# Pointcast_upper_board_V1_02.net
KiCad netlist of a schematic drawn in EAGLE
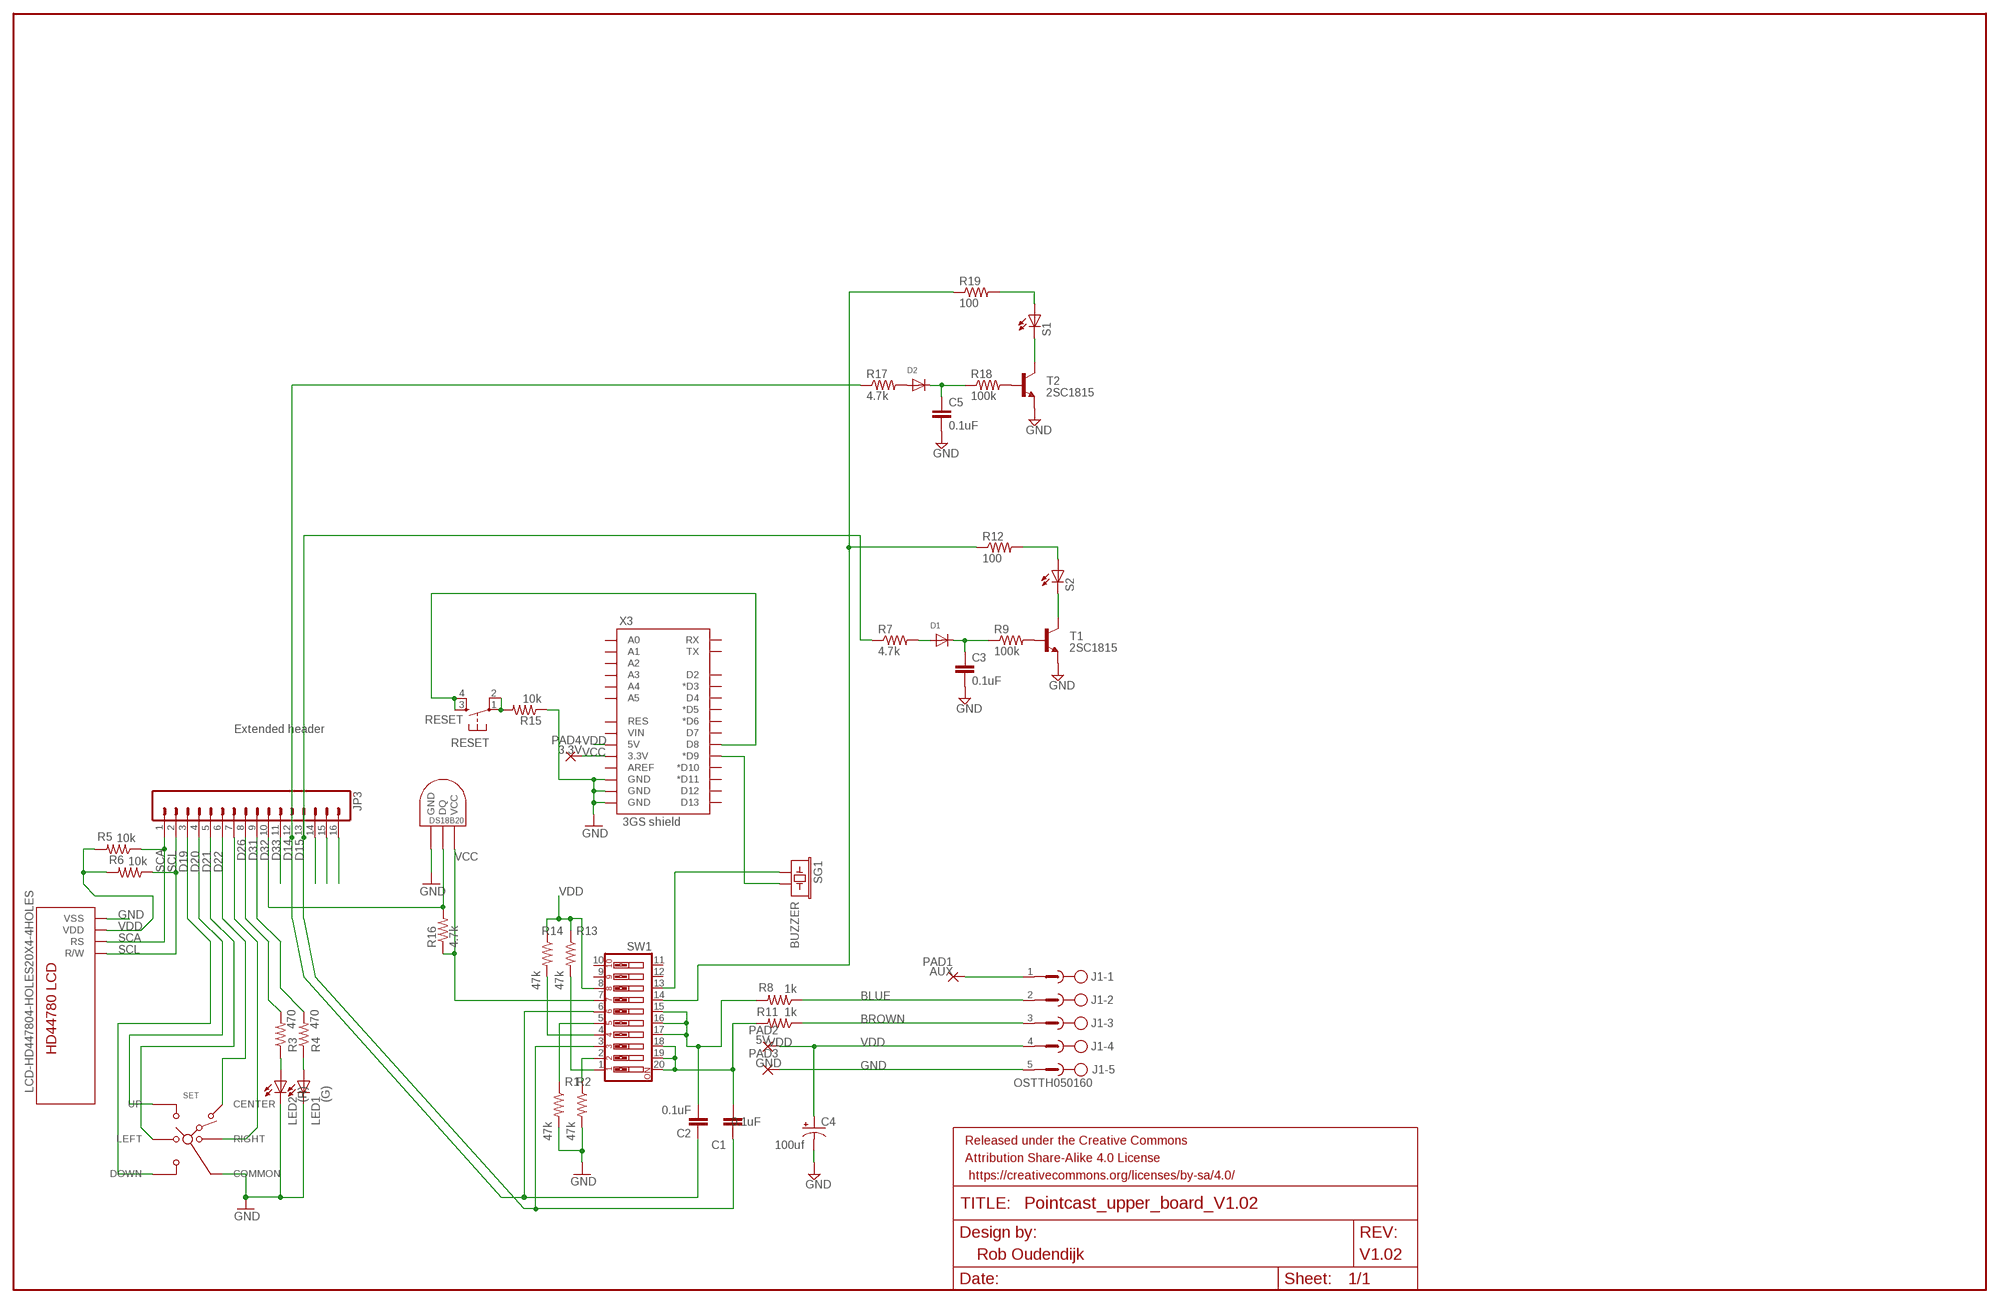
[diagram p0: schematic, sheet 1]

(export (version "E")
  (design (tool "Eeschema 10.0.6"))
  (components
    (comp (ref "C1")
      (value "0.1uF")
      (footprint "eagle-import:C025-024X044")
      (libsource (lib "eagle-import") (part "C-EU025-024X044"))
    )
    (comp (ref "C2")
      (value "0.1uF")
      (footprint "eagle-import:C025-024X044")
      (libsource (lib "eagle-import") (part "C-EU025-024X044"))
    )
    (comp (ref "C3")
      (value "0.1uF")
      (footprint "eagle-import:C025-024X044")
      (libsource (lib "eagle-import") (part "C-EU025-024X044"))
    )
    (comp (ref "C4")
      (value "100uf")
      (footprint "eagle-import:CPOL-RADIAL-100UF-25V")
      (libsource (lib "eagle-import") (part "CAP_POLPTH1"))
    )
    (comp (ref "C5")
      (value "0.1uF")
      (footprint "eagle-import:C025-024X044")
      (libsource (lib "eagle-import") (part "C-EU025-024X044"))
    )
    (comp (ref "D1")
      (value "DIODEDIODE_BIG")
      (footprint "eagle-import:DO41-10")
      (libsource (lib "eagle-import") (part "DIODEDIODE_BIG"))
    )
    (comp (ref "D2")
      (value "DIODEDIODE_BIG")
      (footprint "eagle-import:DO41-10")
      (libsource (lib "eagle-import") (part "DIODEDIODE_BIG"))
    )
    (comp (ref "FRAME1")
      (value "FRAME-LEDGER")
      (footprint "eagle-import:CREATIVE_COMMONS")
      (libsource (lib "eagle-import") (part "FRAME-LEDGER"))
    )
    (comp (ref "J1")
      (value "OSTTH050160")
      (footprint "eagle-import:EDSTL130-05")
      (libsource (lib "eagle-import") (part "OSTTH050160"))
    )
    (comp (ref "JP3")
      (value "Extended header")
      (footprint "eagle-import:1X16")
      (libsource (lib "eagle-import") (part "M16PTH"))
    )
    (comp (ref "LED1")
      (value "(G)")
      (footprint "eagle-import:LED3MM")
      (libsource (lib "eagle-import") (part "LED3MM"))
    )
    (comp (ref "LED2")
      (value "(R)")
      (footprint "eagle-import:LED3MM")
      (libsource (lib "eagle-import") (part "LED3MM"))
    )
    (comp (ref "PAD1")
      (value "AUX")
      (footprint "eagle-import:2,15_1,0")
      (libsource (lib "eagle-import") (part "2,15/1,0"))
    )
    (comp (ref "PAD2")
      (value "5V")
      (footprint "eagle-import:2,15_1,0")
      (libsource (lib "eagle-import") (part "2,15/1,0"))
    )
    (comp (ref "PAD3")
      (value "GND")
      (footprint "eagle-import:2,15_1,0")
      (libsource (lib "eagle-import") (part "2,15/1,0"))
    )
    (comp (ref "PAD4")
      (value "3.3V")
      (footprint "eagle-import:2,15_1,0")
      (libsource (lib "eagle-import") (part "2,15/1,0"))
    )
    (comp (ref "R1")
      (value "47k")
      (footprint "eagle-import:0207_10")
      (libsource (lib "eagle-import") (part "resistor_R-US_0207/10"))
    )
    (comp (ref "R2")
      (value "47k")
      (footprint "eagle-import:0207_10")
      (libsource (lib "eagle-import") (part "resistor_R-US_0207/10"))
    )
    (comp (ref "R3")
      (value "470")
      (footprint "eagle-import:0207_10")
      (libsource (lib "eagle-import") (part "resistor_R-US_0207/10"))
    )
    (comp (ref "R4")
      (value "470")
      (footprint "eagle-import:0207_10")
      (libsource (lib "eagle-import") (part "resistor_R-US_0207/10"))
    )
    (comp (ref "R5")
      (value "10k")
      (footprint "eagle-import:0207_10")
      (libsource (lib "eagle-import") (part "R-US_0207/10"))
    )
    (comp (ref "R6")
      (value "10k")
      (footprint "eagle-import:0207_10")
      (libsource (lib "eagle-import") (part "R-US_0207/10"))
    )
    (comp (ref "R7")
      (value "4.7k")
      (footprint "eagle-import:0207_10")
      (libsource (lib "eagle-import") (part "rcl_R-US_0207/10"))
    )
    (comp (ref "R8")
      (value "1k")
      (footprint "eagle-import:0207_10")
      (libsource (lib "eagle-import") (part "resistor_R-US_0207/10"))
    )
    (comp (ref "R9")
      (value "100k")
      (footprint "eagle-import:0207_10")
      (libsource (lib "eagle-import") (part "rcl_R-US_0207/10"))
    )
    (comp (ref "R11")
      (value "1k")
      (footprint "eagle-import:0207_10")
      (libsource (lib "eagle-import") (part "resistor_R-US_0207/10"))
    )
    (comp (ref "R12")
      (value "100")
      (footprint "eagle-import:0207_10")
      (libsource (lib "eagle-import") (part "rcl_R-US_0207/10"))
    )
    (comp (ref "R13")
      (value "47k")
      (footprint "eagle-import:0207_10")
      (libsource (lib "eagle-import") (part "resistor_R-US_0207/10"))
    )
    (comp (ref "R14")
      (value "47k")
      (footprint "eagle-import:0207_10")
      (libsource (lib "eagle-import") (part "resistor_R-US_0207/10"))
    )
    (comp (ref "R15")
      (value "10k")
      (footprint "eagle-import:0207_10")
      (libsource (lib "eagle-import") (part "resistor_R-US_0207/10"))
    )
    (comp (ref "R16")
      (value "4.7k")
      (footprint "eagle-import:0207_10")
      (libsource (lib "eagle-import") (part "resistor_R-US_0207/10"))
    )
    (comp (ref "R17")
      (value "4.7k")
      (footprint "eagle-import:0207_10")
      (libsource (lib "eagle-import") (part "rcl_R-US_0207/10"))
    )
    (comp (ref "R18")
      (value "100k")
      (footprint "eagle-import:0207_10")
      (libsource (lib "eagle-import") (part "rcl_R-US_0207/10"))
    )
    (comp (ref "R19")
      (value "100")
      (footprint "eagle-import:0207_10")
      (libsource (lib "eagle-import") (part "rcl_R-US_0207/10"))
    )
    (comp (ref "RESET")
      (value "RESET")
      (footprint "eagle-import:DTS-6")
      (libsource (lib "eagle-import") (part "DTS-6"))
    )
    (comp (ref "S1")
      (value "LED3MM")
      (footprint "eagle-import:LED3MM")
      (libsource (lib "eagle-import") (part "LED3MM"))
    )
    (comp (ref "S2")
      (value "LED3MM")
      (footprint "eagle-import:LED3MM")
      (libsource (lib "eagle-import") (part "LED3MM"))
    )
    (comp (ref "SET")
      (value "SKQUCAA010")
      (footprint "eagle-import:SKQU")
      (fields (field (name "MF") "ALPS"))
      (libsource (lib "eagle-import") (part "SKQUCAA010"))
    )
    (comp (ref "SG1")
      (value "BUZZER")
      (footprint "eagle-import:BUZZER-12MM")
      (libsource (lib "eagle-import") (part "BUZZERPTH"))
    )
    (comp (ref "SW1")
      (value "SW_DIP-10")
      (footprint "eagle-import:EDG-10")
      (libsource (lib "eagle-import") (part "SW_DIP-10"))
    )
    (comp (ref "T1")
      (value "2SC1815")
      (footprint "eagle-import:TO92-ECB")
      (libsource (lib "eagle-import") (part "2SC1815"))
    )
    (comp (ref "T2")
      (value "2SC1815")
      (footprint "eagle-import:TO92-ECB")
      (libsource (lib "eagle-import") (part "2SC1815"))
    )
    (comp (ref "TEMP")
      (value "AVA_DS1820TO92")
      (footprint "eagle-import:AVA_DS1820")
      (libsource (lib "eagle-import") (part "AVA_DS1820TO92"))
    )
    (comp (ref "X1")
      (value "LCD-HD447804-HOLES20X4-4HOLES")
      (footprint "eagle-import:LCD-20X4-4HOLES")
      (libsource (lib "eagle-import") (part "LCD-HD4478020X4-4HOLES4-HOLES"))
    )
    (comp (ref "X3")
      (value "3GS shield")
      (footprint "eagle-import:DUEMILANOVE_SHIELD")
      (libsource (lib "eagle-import") (part "ARDUINO_SHIELDLABEL"))
    )
  )
  (nets
    (net (code "1") (name "/BLUE") (class "Default")
      (node (ref "J1") (pin "2") (pinfunction "SK_2") (pintype "passive"))
      (node (ref "R8") (pin "1") (pinfunction "1_1") (pintype "passive"))
    )
    (net (code "2") (name "/BROWN") (class "Default")
      (node (ref "J1") (pin "3") (pinfunction "SK_3") (pintype "passive"))
      (node (ref "R11") (pin "1") (pinfunction "1_1") (pintype "passive"))
    )
    (net (code "3") (name "/D14") (class "Default")
      (node (ref "C2") (pin "1") (pinfunction "1_1") (pintype "passive"))
      (node (ref "JP3") (pin "12") (pinfunction "12_12") (pintype "passive"))
      (node (ref "R17") (pin "1") (pinfunction "1_1") (pintype "passive"))
      (node (ref "SW1") (pin "6") (pinfunction "6_6") (pintype "passive"))
    )
    (net (code "4") (name "/D15") (class "Default")
      (node (ref "C1") (pin "1") (pinfunction "1_1") (pintype "passive"))
      (node (ref "JP3") (pin "13") (pinfunction "13_13") (pintype "passive"))
      (node (ref "R7") (pin "1") (pinfunction "1_1") (pintype "passive"))
      (node (ref "SW1") (pin "3") (pinfunction "3_3") (pintype "passive"))
    )
    (net (code "5") (name "/D19") (class "Default")
      (node (ref "JP3") (pin "3") (pinfunction "3_3") (pintype "passive"))
      (node (ref "SET") (pin "DOWN") (pinfunction "DOWN_DOWN") (pintype "passive"))
    )
    (net (code "6") (name "/D20") (class "Default")
      (node (ref "JP3") (pin "4") (pinfunction "4_4") (pintype "passive"))
      (node (ref "SET") (pin "UP") (pinfunction "UP_UP") (pintype "passive"))
    )
    (net (code "7") (name "/D21") (class "Default")
      (node (ref "JP3") (pin "5") (pinfunction "5_5") (pintype "passive"))
      (node (ref "SET") (pin "LEFT") (pinfunction "LEFT_LEFT") (pintype "passive"))
    )
    (net (code "8") (name "/D22") (class "Default")
      (node (ref "JP3") (pin "6") (pinfunction "6_6") (pintype "passive"))
      (node (ref "SET") (pin "CENTER") (pinfunction "CENTER_CENTER") (pintype "passive"))
    )
    (net (code "9") (name "/D26") (class "Default")
      (node (ref "JP3") (pin "8") (pinfunction "8_8") (pintype "passive"))
      (node (ref "R3") (pin "2") (pinfunction "2_2") (pintype "passive"))
    )
    (net (code "10") (name "/D31") (class "Default")
      (node (ref "JP3") (pin "9") (pinfunction "9_9") (pintype "passive"))
      (node (ref "R4") (pin "2") (pinfunction "2_2") (pintype "passive"))
    )
    (net (code "11") (name "/D32") (class "Default")
      (node (ref "JP3") (pin "10") (pinfunction "10_10") (pintype "passive"))
      (node (ref "R16") (pin "2") (pinfunction "2_2") (pintype "passive"))
      (node (ref "TEMP") (pin "DQ") (pinfunction "DQ_DQ") (pintype "bidirectional"))
    )
    (net (code "12") (name "/D33") (class "Default")
      (node (ref "JP3") (pin "11") (pinfunction "11_11") (pintype "passive"))
    )
    (net (code "13") (name "/SCA") (class "Default")
      (node (ref "JP3") (pin "1") (pinfunction "1_1") (pintype "passive"))
      (node (ref "R5") (pin "1") (pinfunction "1_1") (pintype "passive"))
      (node (ref "X1") (pin "P$15") (pinfunction "RS_P$15") (pintype "input"))
    )
    (net (code "14") (name "/SCL") (class "Default")
      (node (ref "JP3") (pin "2") (pinfunction "2_2") (pintype "passive"))
      (node (ref "R6") (pin "1") (pinfunction "1_1") (pintype "passive"))
      (node (ref "X1") (pin "P$16") (pinfunction "R/W_P$16") (pintype "input"))
    )
    (net (code "15") (name "/VCC") (class "Default")
      (node (ref "PAD4") (pin "1") (pinfunction "P_1") (pintype "passive"))
      (node (ref "R16") (pin "1") (pinfunction "1_1") (pintype "passive"))
      (node (ref "SW1") (pin "7") (pinfunction "7_7") (pintype "passive"))
      (node (ref "TEMP") (pin "VDD") (pinfunction "VCC_VDD") (pintype "power_in"))
      (node (ref "X3") (pin "3.3V") (pinfunction "3.3V_3.3V") (pintype "bidirectional"))
    )
    (net (code "16") (name "/VDD") (class "Default")
      (node (ref "C4") (pin "2") (pinfunction "+_2") (pintype "passive"))
      (node (ref "J1") (pin "4") (pinfunction "SK_4") (pintype "passive"))
      (node (ref "PAD2") (pin "1") (pinfunction "P_1") (pintype "passive"))
      (node (ref "R13") (pin "1") (pinfunction "1_1") (pintype "passive"))
      (node (ref "R14") (pin "1") (pinfunction "1_1") (pintype "passive"))
      (node (ref "R5") (pin "2") (pinfunction "2_2") (pintype "passive"))
      (node (ref "R6") (pin "2") (pinfunction "2_2") (pintype "passive"))
      (node (ref "SW1") (pin "8") (pinfunction "8_8") (pintype "passive"))
      (node (ref "X1") (pin "P$14") (pinfunction "VDD_P$14") (pintype "power_in"))
      (node (ref "X3") (pin "5V") (pinfunction "5V_5V") (pintype "bidirectional"))
    )
    (net (code "17") (name "GND") (class "Default")
      (node (ref "C3") (pin "2") (pinfunction "2_2") (pintype "passive"))
      (node (ref "C4") (pin "1") (pinfunction "-_1") (pintype "passive"))
      (node (ref "C5") (pin "2") (pinfunction "2_2") (pintype "passive"))
      (node (ref "J1") (pin "5") (pinfunction "SK_5") (pintype "passive"))
      (node (ref "LED1") (pin "K") (pinfunction "C_K") (pintype "passive"))
      (node (ref "LED2") (pin "K") (pinfunction "C_K") (pintype "passive"))
      (node (ref "PAD3") (pin "1") (pinfunction "P_1") (pintype "passive"))
      (node (ref "R1") (pin "2") (pinfunction "2_2") (pintype "passive"))
      (node (ref "R15") (pin "1") (pinfunction "1_1") (pintype "passive"))
      (node (ref "R2") (pin "2") (pinfunction "2_2") (pintype "passive"))
      (node (ref "SET") (pin "COMMON") (pinfunction "COMMON_COMMON") (pintype "power_in"))
      (node (ref "T1") (pin "E") (pinfunction "E_E") (pintype "passive"))
      (node (ref "T2") (pin "E") (pinfunction "E_E") (pintype "passive"))
      (node (ref "TEMP") (pin "GND") (pinfunction "GND_GND") (pintype "power_in"))
      (node (ref "X1") (pin "P$13") (pinfunction "VSS_P$13") (pintype "power_in"))
      (node (ref "X3") (pin "GND@0") (pinfunction "GND_GND@0") (pintype "bidirectional"))
      (node (ref "X3") (pin "GND@1") (pinfunction "GND_GND@1") (pintype "bidirectional"))
      (node (ref "X3") (pin "GND@2") (pinfunction "GND_GND@2") (pintype "bidirectional"))
    )
    (net (code "18") (name "Net-(C1-Pad2)") (class "Default")
      (node (ref "C1") (pin "2") (pinfunction "2_2") (pintype "passive"))
      (node (ref "R11") (pin "2") (pinfunction "2_2") (pintype "passive"))
      (node (ref "SW1") (pin "18") (pinfunction "18_18") (pintype "passive"))
      (node (ref "SW1") (pin "19") (pinfunction "19_19") (pintype "passive"))
      (node (ref "SW1") (pin "20") (pinfunction "20_20") (pintype "passive"))
    )
    (net (code "19") (name "Net-(C2-Pad2)") (class "Default")
      (node (ref "C2") (pin "2") (pinfunction "2_2") (pintype "passive"))
      (node (ref "R8") (pin "2") (pinfunction "2_2") (pintype "passive"))
      (node (ref "SW1") (pin "15") (pinfunction "15_15") (pintype "passive"))
      (node (ref "SW1") (pin "16") (pinfunction "16_16") (pintype "passive"))
      (node (ref "SW1") (pin "17") (pinfunction "17_17") (pintype "passive"))
    )
    (net (code "20") (name "Net-(C3-Pad1)") (class "Default")
      (node (ref "C3") (pin "1") (pinfunction "1_1") (pintype "passive"))
      (node (ref "D1") (pin "C") (pinfunction "C_C") (pintype "passive"))
      (node (ref "R9") (pin "1") (pinfunction "1_1") (pintype "passive"))
    )
    (net (code "21") (name "Net-(C5-Pad1)") (class "Default")
      (node (ref "C5") (pin "1") (pinfunction "1_1") (pintype "passive"))
      (node (ref "D2") (pin "C") (pinfunction "C_C") (pintype "passive"))
      (node (ref "R18") (pin "1") (pinfunction "1_1") (pintype "passive"))
    )
    (net (code "22") (name "Net-(D1-PadA)") (class "Default")
      (node (ref "D1") (pin "A") (pinfunction "A_A") (pintype "passive"))
      (node (ref "R7") (pin "2") (pinfunction "2_2") (pintype "passive"))
    )
    (net (code "23") (name "Net-(D2-PadA)") (class "Default")
      (node (ref "D2") (pin "A") (pinfunction "A_A") (pintype "passive"))
      (node (ref "R17") (pin "2") (pinfunction "2_2") (pintype "passive"))
    )
    (net (code "24") (name "Net-(J1A-SK)") (class "Default")
      (node (ref "J1") (pin "1") (pinfunction "SK_1") (pintype "passive"))
      (node (ref "PAD1") (pin "1") (pinfunction "P_1") (pintype "passive"))
    )
    (net (code "25") (name "Net-(JP3-Pad7)") (class "Default")
      (node (ref "JP3") (pin "7") (pinfunction "7_7") (pintype "passive"))
      (node (ref "SET") (pin "RIGHT") (pinfunction "RIGHT_RIGHT") (pintype "passive"))
    )
    (net (code "26") (name "Net-(LED1-PadA)") (class "Default")
      (node (ref "LED1") (pin "A") (pinfunction "A_A") (pintype "passive"))
      (node (ref "R4") (pin "1") (pinfunction "1_1") (pintype "passive"))
    )
    (net (code "27") (name "Net-(LED2-PadA)") (class "Default")
      (node (ref "LED2") (pin "A") (pinfunction "A_A") (pintype "passive"))
      (node (ref "R3") (pin "1") (pinfunction "1_1") (pintype "passive"))
    )
    (net (code "28") (name "Net-(R1-Pad1)") (class "Default")
      (node (ref "R1") (pin "1") (pinfunction "1_1") (pintype "passive"))
      (node (ref "SW1") (pin "5") (pinfunction "5_5") (pintype "passive"))
    )
    (net (code "29") (name "Net-(R2-Pad1)") (class "Default")
      (node (ref "R2") (pin "1") (pinfunction "1_1") (pintype "passive"))
      (node (ref "SW1") (pin "2") (pinfunction "2_2") (pintype "passive"))
    )
    (net (code "30") (name "Net-(R9-Pad2)") (class "Default")
      (node (ref "R9") (pin "2") (pinfunction "2_2") (pintype "passive"))
      (node (ref "T1") (pin "B") (pinfunction "B_B") (pintype "passive"))
    )
    (net (code "31") (name "Net-(R12-Pad1)") (class "Default")
      (node (ref "R12") (pin "1") (pinfunction "1_1") (pintype "passive"))
      (node (ref "R19") (pin "1") (pinfunction "1_1") (pintype "passive"))
      (node (ref "SW1") (pin "14") (pinfunction "14_14") (pintype "passive"))
    )
    (net (code "32") (name "Net-(R12-Pad2)") (class "Default")
      (node (ref "R12") (pin "2") (pinfunction "2_2") (pintype "passive"))
      (node (ref "S2") (pin "A") (pinfunction "A_A") (pintype "passive"))
    )
    (net (code "33") (name "Net-(R13-Pad2)") (class "Default")
      (node (ref "R13") (pin "2") (pinfunction "2_2") (pintype "passive"))
      (node (ref "SW1") (pin "1") (pinfunction "1_1") (pintype "passive"))
    )
    (net (code "34") (name "Net-(R14-Pad2)") (class "Default")
      (node (ref "R14") (pin "2") (pinfunction "2_2") (pintype "passive"))
      (node (ref "SW1") (pin "4") (pinfunction "4_4") (pintype "passive"))
    )
    (net (code "35") (name "Net-(R15-Pad2)") (class "Default")
      (node (ref "R15") (pin "2") (pinfunction "2_2") (pintype "passive"))
      (node (ref "RESET") (pin "1") (pinfunction "1_1") (pintype "passive"))
      (node (ref "RESET") (pin "2") (pinfunction "2_2") (pintype "passive"))
    )
    (net (code "36") (name "Net-(R18-Pad2)") (class "Default")
      (node (ref "R18") (pin "2") (pinfunction "2_2") (pintype "passive"))
      (node (ref "T2") (pin "B") (pinfunction "B_B") (pintype "passive"))
    )
    (net (code "37") (name "Net-(R19-Pad2)") (class "Default")
      (node (ref "R19") (pin "2") (pinfunction "2_2") (pintype "passive"))
      (node (ref "S1") (pin "A") (pinfunction "A_A") (pintype "passive"))
    )
    (net (code "38") (name "Net-(RESET-Pad3)") (class "Default")
      (node (ref "RESET") (pin "3") (pinfunction "3_3") (pintype "passive"))
      (node (ref "RESET") (pin "4") (pinfunction "4_4") (pintype "passive"))
      (node (ref "X3") (pin "D8") (pinfunction "D8_D8") (pintype "bidirectional"))
    )
    (net (code "39") (name "Net-(S1-C)") (class "Default")
      (node (ref "S1") (pin "K") (pinfunction "C_K") (pintype "passive"))
      (node (ref "T2") (pin "C") (pinfunction "C_C") (pintype "passive"))
    )
    (net (code "40") (name "Net-(S2-C)") (class "Default")
      (node (ref "S2") (pin "K") (pinfunction "C_K") (pintype "passive"))
      (node (ref "T1") (pin "C") (pinfunction "C_C") (pintype "passive"))
    )
    (net (code "41") (name "Net-(SG1-1)") (class "Default")
      (node (ref "SG1") (pin "+") (pinfunction "1_+") (pintype "passive"))
      (node (ref "SW1") (pin "13") (pinfunction "13_13") (pintype "passive"))
    )
    (net (code "42") (name "Net-(SG1-2)") (class "Default")
      (node (ref "SG1") (pin "-") (pinfunction "2_-") (pintype "passive"))
      (node (ref "X3") (pin "D9") (pinfunction "*D9_D9") (pintype "bidirectional"))
    )
    (net (code "43") (name "unconnected-(JP3-Pad14)") (class "Default")
      (node (ref "JP3") (pin "14") (pinfunction "14_14") (pintype "passive"))
    )
    (net (code "44") (name "unconnected-(JP3-Pad15)") (class "Default")
      (node (ref "JP3") (pin "15") (pinfunction "15_15") (pintype "passive"))
    )
    (net (code "45") (name "unconnected-(JP3-Pad16)") (class "Default")
      (node (ref "JP3") (pin "16") (pinfunction "16_16") (pintype "passive"))
    )
    (net (code "46") (name "unconnected-(SW1-Pad9)") (class "Default")
      (node (ref "SW1") (pin "9") (pinfunction "9_9") (pintype "passive"))
    )
    (net (code "47") (name "unconnected-(SW1-Pad10)") (class "Default")
      (node (ref "SW1") (pin "10") (pinfunction "10_10") (pintype "passive"))
    )
    (net (code "48") (name "unconnected-(SW1-Pad11)") (class "Default")
      (node (ref "SW1") (pin "11") (pinfunction "11_11") (pintype "passive"))
    )
    (net (code "49") (name "unconnected-(SW1-Pad12)") (class "Default")
      (node (ref "SW1") (pin "12") (pinfunction "12_12") (pintype "passive"))
    )
    (net (code "50") (name "unconnected-(X3-*D3-PadD3)") (class "Default")
      (node (ref "X3") (pin "D3") (pinfunction "*D3_D3") (pintype "bidirectional"))
    )
    (net (code "51") (name "unconnected-(X3-*D5-PadD5)") (class "Default")
      (node (ref "X3") (pin "D5") (pinfunction "*D5_D5") (pintype "bidirectional"))
    )
    (net (code "52") (name "unconnected-(X3-*D6-PadD6)") (class "Default")
      (node (ref "X3") (pin "D6") (pinfunction "*D6_D6") (pintype "bidirectional"))
    )
    (net (code "53") (name "unconnected-(X3-*D10-PadD10)") (class "Default")
      (node (ref "X3") (pin "D10") (pinfunction "*D10_D10") (pintype "bidirectional"))
    )
    (net (code "54") (name "unconnected-(X3-*D11-PadD11)") (class "Default")
      (node (ref "X3") (pin "D11") (pinfunction "*D11_D11") (pintype "bidirectional"))
    )
    (net (code "55") (name "unconnected-(X3-PadA0)") (class "Default")
      (node (ref "X3") (pin "A0") (pinfunction "A0_A0") (pintype "bidirectional"))
    )
    (net (code "56") (name "unconnected-(X3-PadA1)") (class "Default")
      (node (ref "X3") (pin "A1") (pinfunction "A1_A1") (pintype "bidirectional"))
    )
    (net (code "57") (name "unconnected-(X3-PadA2)") (class "Default")
      (node (ref "X3") (pin "A2") (pinfunction "A2_A2") (pintype "bidirectional"))
    )
    (net (code "58") (name "unconnected-(X3-PadA3)") (class "Default")
      (node (ref "X3") (pin "A3") (pinfunction "A3_A3") (pintype "bidirectional"))
    )
    (net (code "59") (name "unconnected-(X3-PadA4)") (class "Default")
      (node (ref "X3") (pin "A4") (pinfunction "A4_A4") (pintype "bidirectional"))
    )
    (net (code "60") (name "unconnected-(X3-PadA5)") (class "Default")
      (node (ref "X3") (pin "A5") (pinfunction "A5_A5") (pintype "bidirectional"))
    )
    (net (code "61") (name "unconnected-(X3-PadAREF)") (class "Default")
      (node (ref "X3") (pin "AREF") (pinfunction "AREF_AREF") (pintype "bidirectional"))
    )
    (net (code "62") (name "unconnected-(X3-PadD2)") (class "Default")
      (node (ref "X3") (pin "D2") (pinfunction "D2_D2") (pintype "bidirectional"))
    )
    (net (code "63") (name "unconnected-(X3-PadD4)") (class "Default")
      (node (ref "X3") (pin "D4") (pinfunction "D4_D4") (pintype "bidirectional"))
    )
    (net (code "64") (name "unconnected-(X3-PadD7)") (class "Default")
      (node (ref "X3") (pin "D7") (pinfunction "D7_D7") (pintype "bidirectional"))
    )
    (net (code "65") (name "unconnected-(X3-PadD12)") (class "Default")
      (node (ref "X3") (pin "D12") (pinfunction "D12_D12") (pintype "bidirectional"))
    )
    (net (code "66") (name "unconnected-(X3-PadD13)") (class "Default")
      (node (ref "X3") (pin "D13") (pinfunction "D13_D13") (pintype "bidirectional"))
    )
    (net (code "67") (name "unconnected-(X3-PadRES)") (class "Default")
      (node (ref "X3") (pin "RES") (pinfunction "RES_RES") (pintype "bidirectional"))
    )
    (net (code "68") (name "unconnected-(X3-PadRX)") (class "Default")
      (node (ref "X3") (pin "RX") (pinfunction "RX_RX") (pintype "bidirectional"))
    )
    (net (code "69") (name "unconnected-(X3-PadTX)") (class "Default")
      (node (ref "X3") (pin "TX") (pinfunction "TX_TX") (pintype "bidirectional"))
    )
    (net (code "70") (name "unconnected-(X3-PadVIN)") (class "Default")
      (node (ref "X3") (pin "VIN") (pinfunction "VIN_VIN") (pintype "bidirectional"))
    )
  )
)
